# SPE_router_top.net
KiCad netlist of a schematic drawn in Altium Designer
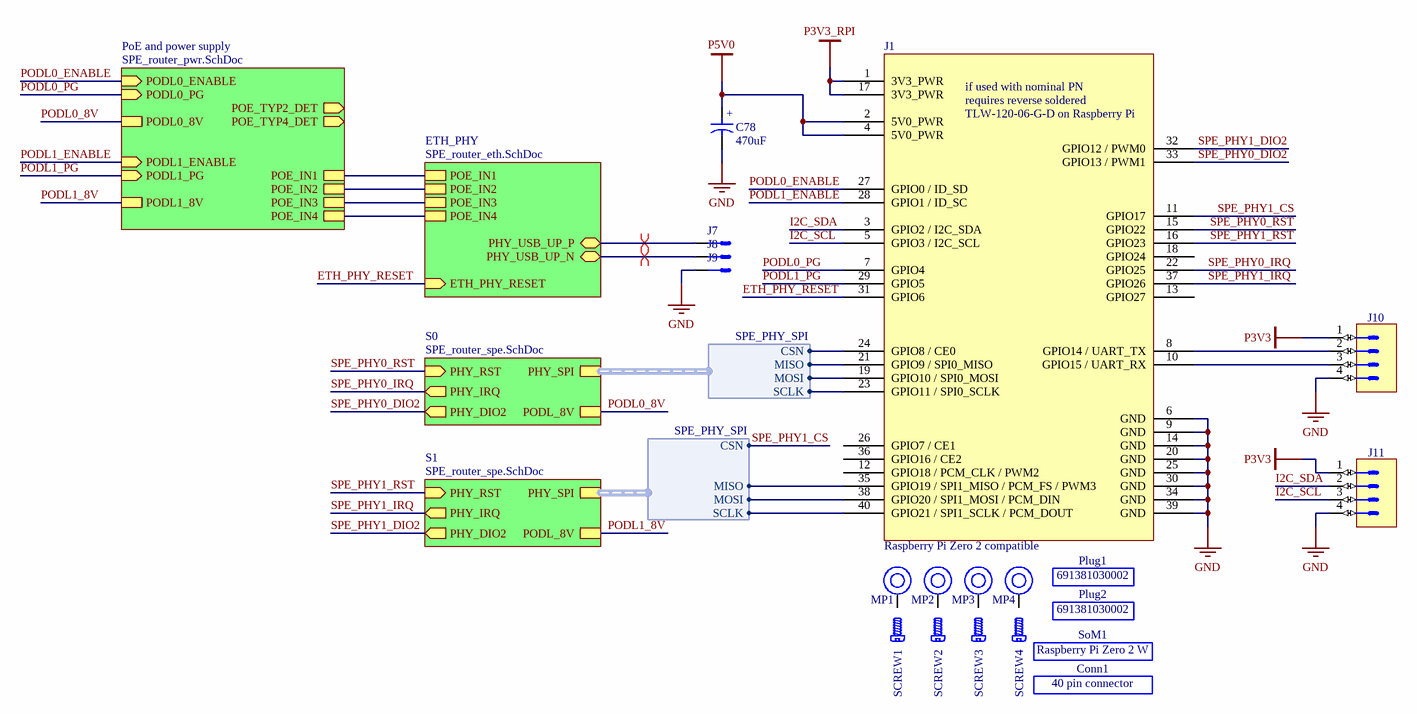
[diagram p0: SPE_router_top.SchDoc]

(export (version "E")
  (design (tool "Eeschema 10.0.6"))
  (components
    (comp (ref "C78")
      (value "470uF")
      (footprint "CAPAE830X1020N")
      (description "Polarised capacitor")
      (fields
        (field (name "PART NUMBER") "CAE830-1020_470UF_16V_20%")
        (field (name "VOLTAGE") "16V")
        (field (name "AUTHOR") "CERN DEM JLC")
      )
      (libsource (lib "Capacitors") (part "Capacitor - polarized"))
    )
    (comp (ref "Conn1")
      (value "40 pin connector")
      (description "Samtec MTLW-120-06-G-D-115")
      (fields
        (field (name "MANUFACTURER") "Samtec")
        (field (name "MANUFACTURER PART NUMBER") "MTLW-120-06-G-D-115")
      )
      (libsource (lib "SPE_router_lib") (part "MTLW-120-06-G-D-115"))
    )
    (comp (ref "J1")
      (value "Raspberry Pi Zero 2 compatible")
      (footprint "SLW-120-01-T-D")
      (description "Conn Socket Strip SKT 40 POS 2.54mm Solder ST Top Entry Thru-Hole Bulk")
      (fields
        (field (name "MANUFACTURER") "Samtec")
        (field (name "MANUFACTURER PART NUMBER") "SLW-120-01-T-D")
      )
      (libsource (lib "SPE_router_lib") (part "SLW-120-01-T-D"))
    )
    (comp (ref "J7")
      (value "0907-4-15-20-75-14-110")
      (footprint "0907-4-15-20-75-14-11-0")
      (description "Conn, Test, Spring Terminal, Plug, Spring Loaded, Pnl Mnt, SMT Term, 1 Cont, Insulated")
      (fields (field (name "MANUFACTURER") "Mill-Max"))
      (libsource (lib "SPE_router_lib") (part "0907-4-15-20-75-14-110"))
    )
    (comp (ref "J8")
      (value "0907-4-15-20-75-14-110")
      (footprint "0907-4-15-20-75-14-11-0")
      (description "Conn, Test, Spring Terminal, Plug, Spring Loaded, Pnl Mnt, SMT Term, 1 Cont, Insulated")
      (fields (field (name "MANUFACTURER") "Mill-Max"))
      (libsource (lib "SPE_router_lib") (part "0907-4-15-20-75-14-110"))
    )
    (comp (ref "J9")
      (value "0907-4-15-20-75-14-110")
      (footprint "0907-4-15-20-75-14-11-0")
      (description "Conn, Test, Spring Terminal, Plug, Spring Loaded, Pnl Mnt, SMT Term, 1 Cont, Insulated")
      (fields (field (name "MANUFACTURER") "Mill-Max"))
      (libsource (lib "SPE_router_lib") (part "0907-4-15-20-75-14-110"))
    )
    (comp (ref "J10")
      (value "Header 4")
      (footprint "SAMTEC_TSW-104-07-L-S-LL")
      (description "Connector 4 Male")
      (fields
        (field (name "PART NUMBER") "SAMTEC_TSW-104-07-L-S-LL")
        (field (name "MANUFACTURER") "SAMTEC")
        (field (name "AUTHOR") "CERN DEM MR")
      )
      (libsource (lib "Connectors") (part "Connector 4 Male"))
    )
    (comp (ref "J11")
      (value "Header 4")
      (footprint "SAMTEC_TSW-104-07-L-S-LL")
      (description "Connector 4 Male")
      (fields
        (field (name "PART NUMBER") "SAMTEC_TSW-104-07-L-S-LL")
        (field (name "MANUFACTURER") "SAMTEC")
        (field (name "AUTHOR") "CERN DEM MR")
      )
      (libsource (lib "Connectors") (part "Connector 4 Male"))
    )
    (comp (ref "MP1")
      (value "M2.5 x 6.5mm")
      (footprint "9774065151")
      (description "WA-SMSI SMT Steel Spacer with internal Thread, OD 5.1mm, M2.5 x 6.5mm")
      (fields
        (field (name "MANUFACTURER PART NUMBER") "9774065151R")
        (field (name "MANUFACTURER") "Wurth Elektronik")
      )
      (libsource (lib "SPE_router_lib") (part "9774065151R"))
    )
    (comp (ref "MP2")
      (value "M2.5 x 6.5mm")
      (footprint "9774065151")
      (description "WA-SMSI SMT Steel Spacer with internal Thread, OD 5.1mm, M2.5 x 6.5mm")
      (fields
        (field (name "MANUFACTURER PART NUMBER") "9774065151R")
        (field (name "MANUFACTURER") "Wurth Elektronik")
      )
      (libsource (lib "SPE_router_lib") (part "9774065151R"))
    )
    (comp (ref "MP3")
      (value "M2.5 x 6.5mm")
      (footprint "9774065151")
      (description "WA-SMSI SMT Steel Spacer with internal Thread, OD 5.1mm, M2.5 x 6.5mm")
      (fields
        (field (name "MANUFACTURER PART NUMBER") "9774065151R")
        (field (name "MANUFACTURER") "Wurth Elektronik")
      )
      (libsource (lib "SPE_router_lib") (part "9774065151R"))
    )
    (comp (ref "MP4")
      (value "M2.5 x 6.5mm")
      (footprint "9774065151")
      (description "WA-SMSI SMT Steel Spacer with internal Thread, OD 5.1mm, M2.5 x 6.5mm")
      (fields
        (field (name "MANUFACTURER PART NUMBER") "9774065151R")
        (field (name "MANUFACTURER") "Wurth Elektronik")
      )
      (libsource (lib "SPE_router_lib") (part "9774065151R"))
    )
    (comp (ref "Plug1")
      (value "691381030002")
      (description "Wurth Elektronik 691381030002")
      (fields (field (name "MANUFACTURER") "Wurth Elektronik"))
      (libsource (lib "SPE_router_lib") (part "691381030002"))
    )
    (comp (ref "Plug2")
      (value "691381030002")
      (description "Wurth Elektronik 691381030002")
      (fields (field (name "MANUFACTURER") "Wurth Elektronik"))
      (libsource (lib "SPE_router_lib") (part "691381030002"))
    )
    (comp (ref "SCREW1")
      (value "RM2.5x6MM 2701")
      (description "Screw")
      (fields (field (name "MANUFACTURER") "APM HEXSEAL"))
      (libsource (lib "SPE_router_lib") (part "RM2.5x6MM 2701"))
    )
    (comp (ref "SCREW2")
      (value "RM2.5x6MM 2701")
      (description "Screw")
      (fields (field (name "MANUFACTURER") "APM HEXSEAL"))
      (libsource (lib "SPE_router_lib") (part "RM2.5x6MM 2701"))
    )
    (comp (ref "SCREW3")
      (value "RM2.5x6MM 2701")
      (description "Screw")
      (fields (field (name "MANUFACTURER") "APM HEXSEAL"))
      (libsource (lib "SPE_router_lib") (part "RM2.5x6MM 2701"))
    )
    (comp (ref "SCREW4")
      (value "RM2.5x6MM 2701")
      (description "Screw")
      (fields (field (name "MANUFACTURER") "APM HEXSEAL"))
      (libsource (lib "SPE_router_lib") (part "RM2.5x6MM 2701"))
    )
    (comp (ref "SoM1")
      (value "Raspberry Pi Zero 2 W")
      (fields (field (name "MANUFACTURER") "Raspberry Pi") (field (name "MANUFACTURER PART NUMBER") "SC0510"))
      (libsource (lib "SPE_router_lib") (part "SC0510"))
    )
  )
  (nets
    (net (code "2") (name "/ETH_PHY_RESET") (class "Default")
      (node (ref "J1") (pin "31") (pinfunction "GPIO6_31") (pintype "passive"))
    )
    (net (code "3") (name "/I2C_SCL") (class "Default")
      (node (ref "J1") (pin "5") (pinfunction "GPIO3_/_I2C_SCL_5") (pintype "passive"))
      (node (ref "J11") (pin "3") (pinfunction "3_3") (pintype "bidirectional"))
    )
    (net (code "4") (name "/I2C_SDA") (class "Default")
      (node (ref "J1") (pin "3") (pinfunction "GPIO2_/_I2C_SDA_3") (pintype "passive"))
      (node (ref "J11") (pin "2") (pinfunction "2_2") (pintype "bidirectional"))
    )
    (net (code "5") (name "/PHY_USB_UP_N") (class "Default")
      (node (ref "J8") (pin "1") (pinfunction "1_1") (pintype "bidirectional"))
    )
    (net (code "6") (name "/PHY_USB_UP_P") (class "Default")
      (node (ref "J7") (pin "1") (pinfunction "1_1") (pintype "bidirectional"))
    )
    (net (code "8") (name "/PODL0_ENABLE") (class "Default")
      (node (ref "J1") (pin "27") (pinfunction "GPIO0_/_ID_SD_27") (pintype "passive"))
    )
    (net (code "9") (name "/PODL0_PG") (class "Default")
      (node (ref "J1") (pin "7") (pinfunction "GPIO4_7") (pintype "passive"))
    )
    (net (code "11") (name "/PODL1_ENABLE") (class "Default")
      (node (ref "J1") (pin "28") (pinfunction "GPIO1_/_ID_SC_28") (pintype "passive"))
    )
    (net (code "12") (name "/PODL1_PG") (class "Default")
      (node (ref "J1") (pin "29") (pinfunction "GPIO5_29") (pintype "passive"))
    )
    (net (code "19") (name "/SPE_PHY0_DIO2") (class "Default")
      (node (ref "J1") (pin "33") (pinfunction "GPIO13_/_PWM1_33") (pintype "passive"))
    )
    (net (code "20") (name "/SPE_PHY0_IRQ") (class "Default")
      (node (ref "J1") (pin "22") (pinfunction "GPIO25_22") (pintype "passive"))
    )
    (net (code "21") (name "/SPE_PHY0_RST") (class "Default")
      (node (ref "J1") (pin "15") (pinfunction "GPIO22_15") (pintype "passive"))
    )
    (net (code "22") (name "/SPE_PHY1_CS") (class "Default")
      (node (ref "J1") (pin "11") (pinfunction "GPIO17_11") (pintype "passive"))
    )
    (net (code "23") (name "/SPE_PHY1_DIO2") (class "Default")
      (node (ref "J1") (pin "32") (pinfunction "GPIO12_/_PWM0_32") (pintype "passive"))
    )
    (net (code "24") (name "/SPE_PHY1_IRQ") (class "Default")
      (node (ref "J1") (pin "37") (pinfunction "GPIO26_37") (pintype "passive"))
    )
    (net (code "25") (name "/SPE_PHY1_RST") (class "Default")
      (node (ref "J1") (pin "16") (pinfunction "GPIO23_16") (pintype "passive"))
    )
    (net (code "27") (name "GND") (class "Default")
      (node (ref "C78") (pin "2") (pinfunction "2_2") (pintype "passive"))
      (node (ref "J1") (pin "14") (pinfunction "GND_14") (pintype "passive"))
      (node (ref "J1") (pin "20") (pinfunction "GND_20") (pintype "passive"))
      (node (ref "J1") (pin "25") (pinfunction "GND_25") (pintype "passive"))
      (node (ref "J1") (pin "30") (pinfunction "GND_30") (pintype "passive"))
      (node (ref "J1") (pin "34") (pinfunction "GND_34") (pintype "passive"))
      (node (ref "J1") (pin "39") (pinfunction "GND_39") (pintype "passive"))
      (node (ref "J1") (pin "6") (pinfunction "GND_6") (pintype "passive"))
      (node (ref "J1") (pin "9") (pinfunction "GND_9") (pintype "passive"))
      (node (ref "J10") (pin "4") (pinfunction "4_4") (pintype "bidirectional"))
      (node (ref "J11") (pin "4") (pinfunction "4_4") (pintype "bidirectional"))
      (node (ref "J9") (pin "1") (pinfunction "1_1") (pintype "bidirectional"))
    )
    (net (code "28") (name "Net-(J1-GPIO14_{slash}_UART_TX)") (class "Default")
      (node (ref "J1") (pin "8") (pinfunction "GPIO14_/_UART_TX_8") (pintype "passive"))
      (node (ref "J10") (pin "2") (pinfunction "2_2") (pintype "bidirectional"))
    )
    (net (code "29") (name "Net-(J1-GPIO15_{slash}_UART_RX)") (class "Default")
      (node (ref "J1") (pin "10") (pinfunction "GPIO15_/_UART_RX_10") (pintype "passive"))
      (node (ref "J10") (pin "3") (pinfunction "3_3") (pintype "bidirectional"))
    )
    (net (code "30") (name "P3V3") (class "Default")
      (node (ref "J10") (pin "1") (pinfunction "1_1") (pintype "bidirectional"))
      (node (ref "J11") (pin "1") (pinfunction "1_1") (pintype "bidirectional"))
    )
    (net (code "31") (name "P3V3_RPI") (class "Default")
      (node (ref "J1") (pin "1") (pinfunction "3V3_PWR_1") (pintype "passive"))
      (node (ref "J1") (pin "17") (pinfunction "3V3_PWR_17") (pintype "passive"))
    )
    (net (code "32") (name "P5V0") (class "Default")
      (node (ref "C78") (pin "1") (pinfunction "1_1") (pintype "passive"))
      (node (ref "J1") (pin "2") (pinfunction "5V0_PWR_2") (pintype "passive"))
      (node (ref "J1") (pin "4") (pinfunction "5V0_PWR_4") (pintype "passive"))
    )
    (net (code "33") (name "unconnected-(J1-GPIO7_{slash}_CE1-Pad26)") (class "Default")
      (node (ref "J1") (pin "26") (pinfunction "GPIO7_/_CE1_26") (pintype "passive"))
    )
    (net (code "34") (name "unconnected-(J1-GPIO8_{slash}_CE0-Pad24)") (class "Default")
      (node (ref "J1") (pin "24") (pinfunction "GPIO8_/_CE0_24") (pintype "passive"))
    )
    (net (code "35") (name "unconnected-(J1-GPIO9_{slash}_SPI0_MISO-Pad21)") (class "Default")
      (node (ref "J1") (pin "21") (pinfunction "GPIO9_/_SPI0_MISO_21") (pintype "passive"))
    )
    (net (code "36") (name "unconnected-(J1-GPIO10_{slash}_SPI0_MOSI-Pad19)") (class "Default")
      (node (ref "J1") (pin "19") (pinfunction "GPIO10_/_SPI0_MOSI_19") (pintype "passive"))
    )
    (net (code "37") (name "unconnected-(J1-GPIO11_{slash}_SPI0_SCLK-Pad23)") (class "Default")
      (node (ref "J1") (pin "23") (pinfunction "GPIO11_/_SPI0_SCLK_23") (pintype "passive"))
    )
    (net (code "38") (name "unconnected-(J1-GPIO16_{slash}_CE2-Pad36)") (class "Default")
      (node (ref "J1") (pin "36") (pinfunction "GPIO16_/_CE2_36") (pintype "passive"))
    )
    (net (code "39") (name "unconnected-(J1-GPIO18_{slash}_PCM_CLK_{slash}_PWM2-Pad12)") (class "Default")
      (node (ref "J1") (pin "12") (pinfunction "GPIO18_/_PCM_CLK_/_PWM2_12") (pintype "passive"))
    )
    (net (code "40") (name "unconnected-(J1-GPIO19_{slash}_SPI1_MISO_{slash}_PCM_FS_{slash}_PWM3-Pad35)") (class "Default")
      (node (ref "J1") (pin "35") (pinfunction "GPIO19_/_SPI1_MISO_/_PCM_FS_/_PWM3_35") (pintype "passive"))
    )
    (net (code "41") (name "unconnected-(J1-GPIO20_{slash}_SPI1_MOSI_{slash}_PCM_DIN-Pad38)") (class "Default")
      (node (ref "J1") (pin "38") (pinfunction "GPIO20_/_SPI1_MOSI_/_PCM_DIN_38") (pintype "passive"))
    )
    (net (code "42") (name "unconnected-(J1-GPIO21_{slash}_SPI1_SCLK_{slash}_PCM_DOUT-Pad40)") (class "Default")
      (node (ref "J1") (pin "40") (pinfunction "GPIO21_/_SPI1_SCLK_/_PCM_DOUT_40") (pintype "passive"))
    )
    (net (code "43") (name "unconnected-(J1-GPIO24-Pad18)") (class "Default")
      (node (ref "J1") (pin "18") (pinfunction "GPIO24_18") (pintype "passive"))
    )
    (net (code "44") (name "unconnected-(J1-GPIO27-Pad13)") (class "Default")
      (node (ref "J1") (pin "13") (pinfunction "GPIO27_13") (pintype "passive"))
    )
    (net (code "45") (name "unconnected-(MP1-Pad1)") (class "Default")
      (node (ref "MP1") (pin "1") (pinfunction "1_1") (pintype "passive"))
    )
    (net (code "46") (name "unconnected-(MP2-Pad1)") (class "Default")
      (node (ref "MP2") (pin "1") (pinfunction "1_1") (pintype "passive"))
    )
    (net (code "47") (name "unconnected-(MP3-Pad1)") (class "Default")
      (node (ref "MP3") (pin "1") (pinfunction "1_1") (pintype "passive"))
    )
    (net (code "48") (name "unconnected-(MP4-Pad1)") (class "Default")
      (node (ref "MP4") (pin "1") (pinfunction "1_1") (pintype "passive"))
    )
  )
)
